# mcp23s08.net
KiCad netlist of a schematic drawn in EAGLE
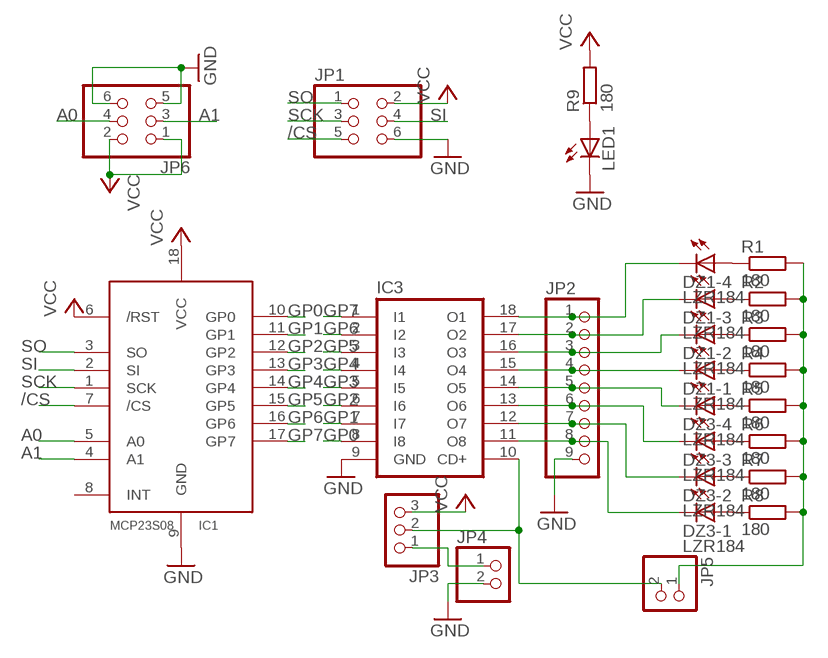
[diagram p0: schematic, sheet 1]

(export (version "E")
  (design (tool "Eeschema 10.0.6"))
  (components
    (comp (ref "DZ1")
      (value "LZR184")
      (footprint "eagle-import:LZR184")
      (libsource (lib "eagle-import") (part "LZR184"))
    )
    (comp (ref "DZ3")
      (value "LZR184")
      (footprint "eagle-import:LZR184")
      (libsource (lib "eagle-import") (part "LZR184"))
    )
    (comp (ref "IC1")
      (value "MCP2300X/P")
      (footprint "eagle-import:DIL18")
      (libsource (lib "eagle-import") (part "MCP2300X/P"))
    )
    (comp (ref "IC3")
      (value "ULN2803A")
      (footprint "eagle-import:DIL18")
      (libsource (lib "eagle-import") (part "ULN2803A"))
    )
    (comp (ref "JP1")
      (value "PINHD-2X3")
      (footprint "eagle-import:2X03")
      (libsource (lib "eagle-import") (part "PINHD-2X3"))
    )
    (comp (ref "JP2")
      (value "PINHD-1X9")
      (footprint "eagle-import:1X09")
      (libsource (lib "eagle-import") (part "PINHD-1X9"))
    )
    (comp (ref "JP3")
      (value "PINHD-1X3")
      (footprint "eagle-import:1X03")
      (libsource (lib "eagle-import") (part "PINHD-1X3"))
    )
    (comp (ref "JP4")
      (value "PINHD-1X2")
      (footprint "eagle-import:1X02")
      (libsource (lib "eagle-import") (part "PINHD-1X2"))
    )
    (comp (ref "JP5")
      (value "PINHD-1X2")
      (footprint "eagle-import:1X02")
      (libsource (lib "eagle-import") (part "PINHD-1X2"))
    )
    (comp (ref "JP6")
      (value "PINHD-2X3")
      (footprint "eagle-import:2X03")
      (libsource (lib "eagle-import") (part "PINHD-2X3"))
    )
    (comp (ref "LED1")
      (value "LED3MM")
      (footprint "eagle-import:LED3MM")
      (libsource (lib "eagle-import") (part "LED3MM"))
    )
    (comp (ref "R1")
      (value "180")
      (footprint "eagle-import:0204V")
      (libsource (lib "eagle-import") (part "R-EU_0204/2V"))
    )
    (comp (ref "R2")
      (value "180")
      (footprint "eagle-import:0204V")
      (libsource (lib "eagle-import") (part "R-EU_0204/2V"))
    )
    (comp (ref "R3")
      (value "180")
      (footprint "eagle-import:0204V")
      (libsource (lib "eagle-import") (part "R-EU_0204/2V"))
    )
    (comp (ref "R4")
      (value "180")
      (footprint "eagle-import:0204V")
      (libsource (lib "eagle-import") (part "R-EU_0204/2V"))
    )
    (comp (ref "R5")
      (value "180")
      (footprint "eagle-import:0204V")
      (libsource (lib "eagle-import") (part "R-EU_0204/2V"))
    )
    (comp (ref "R6")
      (value "180")
      (footprint "eagle-import:0204V")
      (libsource (lib "eagle-import") (part "R-EU_0204/2V"))
    )
    (comp (ref "R7")
      (value "180")
      (footprint "eagle-import:0204V")
      (libsource (lib "eagle-import") (part "R-EU_0204/2V"))
    )
    (comp (ref "R8")
      (value "180")
      (footprint "eagle-import:0204V")
      (libsource (lib "eagle-import") (part "R-EU_0204/2V"))
    )
    (comp (ref "R9")
      (value "180")
      (footprint "eagle-import:0204V")
      (libsource (lib "eagle-import") (part "R-EU_0204/2V"))
    )
  )
  (nets
    (net (code "1") (name "/A0") (class "Default")
      (node (ref "IC1") (pin "5") (pinfunction "A0_5") (pintype "input"))
      (node (ref "JP6") (pin "4") (pinfunction "4_4") (pintype "passive"))
    )
    (net (code "2") (name "/A1") (class "Default")
      (node (ref "IC1") (pin "4") (pinfunction "A1_4") (pintype "input"))
      (node (ref "JP6") (pin "3") (pinfunction "3_3") (pintype "passive"))
    )
    (net (code "3") (name "/GP0") (class "Default")
      (node (ref "IC1") (pin "10") (pinfunction "GP0_10") (pintype "bidirectional"))
      (node (ref "IC3") (pin "8") (pinfunction "I8_8") (pintype "input"))
    )
    (net (code "4") (name "/GP1") (class "Default")
      (node (ref "IC1") (pin "11") (pinfunction "GP1_11") (pintype "bidirectional"))
      (node (ref "IC3") (pin "7") (pinfunction "I7_7") (pintype "input"))
    )
    (net (code "5") (name "/GP2") (class "Default")
      (node (ref "IC1") (pin "12") (pinfunction "GP2_12") (pintype "bidirectional"))
      (node (ref "IC3") (pin "6") (pinfunction "I6_6") (pintype "input"))
    )
    (net (code "6") (name "/GP3") (class "Default")
      (node (ref "IC1") (pin "13") (pinfunction "GP3_13") (pintype "bidirectional"))
      (node (ref "IC3") (pin "5") (pinfunction "I5_5") (pintype "input"))
    )
    (net (code "7") (name "/GP4") (class "Default")
      (node (ref "IC1") (pin "14") (pinfunction "GP4_14") (pintype "bidirectional"))
      (node (ref "IC3") (pin "4") (pinfunction "I4_4") (pintype "input"))
    )
    (net (code "8") (name "/GP5") (class "Default")
      (node (ref "IC1") (pin "15") (pinfunction "GP5_15") (pintype "bidirectional"))
      (node (ref "IC3") (pin "3") (pinfunction "I3_3") (pintype "input"))
    )
    (net (code "9") (name "/GP6") (class "Default")
      (node (ref "IC1") (pin "16") (pinfunction "GP6_16") (pintype "bidirectional"))
      (node (ref "IC3") (pin "2") (pinfunction "I2_2") (pintype "input"))
    )
    (net (code "10") (name "/GP7") (class "Default")
      (node (ref "IC1") (pin "17") (pinfunction "GP7_17") (pintype "bidirectional"))
      (node (ref "IC3") (pin "1") (pinfunction "I1_1") (pintype "input"))
    )
    (net (code "11") (name "/SCK") (class "Default")
      (node (ref "IC1") (pin "1") (pinfunction "SCK_1") (pintype "bidirectional"))
      (node (ref "JP1") (pin "3") (pinfunction "3_3") (pintype "passive"))
    )
    (net (code "12") (name "/SI") (class "Default")
      (node (ref "IC1") (pin "2") (pinfunction "SI_2") (pintype "bidirectional"))
      (node (ref "JP1") (pin "4") (pinfunction "4_4") (pintype "passive"))
    )
    (net (code "13") (name "/SO") (class "Default")
      (node (ref "IC1") (pin "3") (pinfunction "SO_3") (pintype "output"))
      (node (ref "JP1") (pin "1") (pinfunction "1_1") (pintype "passive"))
    )
    (net (code "14") (name "/{slash}CS") (class "Default")
      (node (ref "IC1") (pin "7") (pinfunction "/CS_7") (pintype "input"))
      (node (ref "JP1") (pin "5") (pinfunction "5_5") (pintype "passive"))
    )
    (net (code "15") (name "GND") (class "Default")
      (node (ref "IC1") (pin "9") (pinfunction "GND_9") (pintype "power_in"))
      (node (ref "IC3") (pin "9") (pinfunction "GND_9") (pintype "power_in"))
      (node (ref "JP1") (pin "6") (pinfunction "6_6") (pintype "passive"))
      (node (ref "JP2") (pin "9") (pinfunction "9_9") (pintype "passive"))
      (node (ref "JP4") (pin "2") (pinfunction "2_2") (pintype "passive"))
      (node (ref "JP6") (pin "5") (pinfunction "5_5") (pintype "passive"))
      (node (ref "JP6") (pin "6") (pinfunction "6_6") (pintype "passive"))
      (node (ref "LED1") (pin "K") (pinfunction "C_K") (pintype "passive"))
    )
    (net (code "16") (name "Net-(DZ1A-A)") (class "Default")
      (node (ref "DZ1") (pin "A1") (pinfunction "A_A1") (pintype "passive"))
      (node (ref "R4") (pin "1") (pinfunction "1_1") (pintype "passive"))
    )
    (net (code "17") (name "Net-(DZ1A-C)") (class "Default")
      (node (ref "DZ1") (pin "K1") (pinfunction "C_K1") (pintype "passive"))
      (node (ref "IC3") (pin "15") (pinfunction "O4_15") (pintype "open_collector"))
      (node (ref "JP2") (pin "4") (pinfunction "4_4") (pintype "passive"))
    )
    (net (code "18") (name "Net-(DZ1B-A)") (class "Default")
      (node (ref "DZ1") (pin "A2") (pinfunction "A_A2") (pintype "passive"))
      (node (ref "R3") (pin "1") (pinfunction "1_1") (pintype "passive"))
    )
    (net (code "19") (name "Net-(DZ1B-C)") (class "Default")
      (node (ref "DZ1") (pin "K2") (pinfunction "C_K2") (pintype "passive"))
      (node (ref "IC3") (pin "16") (pinfunction "O3_16") (pintype "open_collector"))
      (node (ref "JP2") (pin "3") (pinfunction "3_3") (pintype "passive"))
    )
    (net (code "20") (name "Net-(DZ1C-A)") (class "Default")
      (node (ref "DZ1") (pin "A3") (pinfunction "A_A3") (pintype "passive"))
      (node (ref "R2") (pin "1") (pinfunction "1_1") (pintype "passive"))
    )
    (net (code "21") (name "Net-(DZ1C-C)") (class "Default")
      (node (ref "DZ1") (pin "K3") (pinfunction "C_K3") (pintype "passive"))
      (node (ref "IC3") (pin "17") (pinfunction "O2_17") (pintype "open_collector"))
      (node (ref "JP2") (pin "2") (pinfunction "2_2") (pintype "passive"))
    )
    (net (code "22") (name "Net-(DZ1D-A)") (class "Default")
      (node (ref "DZ1") (pin "A4") (pinfunction "A_A4") (pintype "passive"))
      (node (ref "R1") (pin "1") (pinfunction "1_1") (pintype "passive"))
    )
    (net (code "23") (name "Net-(DZ1D-C)") (class "Default")
      (node (ref "DZ1") (pin "K4") (pinfunction "C_K4") (pintype "passive"))
      (node (ref "IC3") (pin "18") (pinfunction "O1_18") (pintype "open_collector"))
      (node (ref "JP2") (pin "1") (pinfunction "1_1") (pintype "passive"))
    )
    (net (code "24") (name "Net-(DZ3A-A)") (class "Default")
      (node (ref "DZ3") (pin "A1") (pinfunction "A_A1") (pintype "passive"))
      (node (ref "R8") (pin "1") (pinfunction "1_1") (pintype "passive"))
    )
    (net (code "25") (name "Net-(DZ3A-C)") (class "Default")
      (node (ref "DZ3") (pin "K1") (pinfunction "C_K1") (pintype "passive"))
      (node (ref "IC3") (pin "11") (pinfunction "O8_11") (pintype "open_collector"))
      (node (ref "JP2") (pin "8") (pinfunction "8_8") (pintype "passive"))
    )
    (net (code "26") (name "Net-(DZ3B-A)") (class "Default")
      (node (ref "DZ3") (pin "A2") (pinfunction "A_A2") (pintype "passive"))
      (node (ref "R7") (pin "1") (pinfunction "1_1") (pintype "passive"))
    )
    (net (code "27") (name "Net-(DZ3B-C)") (class "Default")
      (node (ref "DZ3") (pin "K2") (pinfunction "C_K2") (pintype "passive"))
      (node (ref "IC3") (pin "12") (pinfunction "O7_12") (pintype "open_collector"))
      (node (ref "JP2") (pin "7") (pinfunction "7_7") (pintype "passive"))
    )
    (net (code "28") (name "Net-(DZ3C-A)") (class "Default")
      (node (ref "DZ3") (pin "A3") (pinfunction "A_A3") (pintype "passive"))
      (node (ref "R6") (pin "1") (pinfunction "1_1") (pintype "passive"))
    )
    (net (code "29") (name "Net-(DZ3C-C)") (class "Default")
      (node (ref "DZ3") (pin "K3") (pinfunction "C_K3") (pintype "passive"))
      (node (ref "IC3") (pin "13") (pinfunction "O6_13") (pintype "open_collector"))
      (node (ref "JP2") (pin "6") (pinfunction "6_6") (pintype "passive"))
    )
    (net (code "30") (name "Net-(DZ3D-A)") (class "Default")
      (node (ref "DZ3") (pin "A4") (pinfunction "A_A4") (pintype "passive"))
      (node (ref "R5") (pin "1") (pinfunction "1_1") (pintype "passive"))
    )
    (net (code "31") (name "Net-(DZ3D-C)") (class "Default")
      (node (ref "DZ3") (pin "K4") (pinfunction "C_K4") (pintype "passive"))
      (node (ref "IC3") (pin "14") (pinfunction "O5_14") (pintype "open_collector"))
      (node (ref "JP2") (pin "5") (pinfunction "5_5") (pintype "passive"))
    )
    (net (code "32") (name "Net-(IC3-CD+)") (class "Default")
      (node (ref "IC3") (pin "10") (pinfunction "CD+_10") (pintype "passive"))
      (node (ref "JP3") (pin "2") (pinfunction "2_2") (pintype "passive"))
      (node (ref "JP5") (pin "2") (pinfunction "2_2") (pintype "passive"))
    )
    (net (code "33") (name "Net-(JP3-Pad1)") (class "Default")
      (node (ref "JP3") (pin "1") (pinfunction "1_1") (pintype "passive"))
      (node (ref "JP4") (pin "1") (pinfunction "1_1") (pintype "passive"))
    )
    (net (code "34") (name "Net-(JP5-Pad1)") (class "Default")
      (node (ref "JP5") (pin "1") (pinfunction "1_1") (pintype "passive"))
      (node (ref "R1") (pin "2") (pinfunction "2_2") (pintype "passive"))
      (node (ref "R2") (pin "2") (pinfunction "2_2") (pintype "passive"))
      (node (ref "R3") (pin "2") (pinfunction "2_2") (pintype "passive"))
      (node (ref "R4") (pin "2") (pinfunction "2_2") (pintype "passive"))
      (node (ref "R5") (pin "2") (pinfunction "2_2") (pintype "passive"))
      (node (ref "R6") (pin "2") (pinfunction "2_2") (pintype "passive"))
      (node (ref "R7") (pin "2") (pinfunction "2_2") (pintype "passive"))
      (node (ref "R8") (pin "2") (pinfunction "2_2") (pintype "passive"))
    )
    (net (code "35") (name "Net-(LED1-PadA)") (class "Default")
      (node (ref "LED1") (pin "A") (pinfunction "A_A") (pintype "passive"))
      (node (ref "R9") (pin "1") (pinfunction "1_1") (pintype "passive"))
    )
    (net (code "36") (name "VCC") (class "Default")
      (node (ref "IC1") (pin "18") (pinfunction "VCC_18") (pintype "power_in"))
      (node (ref "IC1") (pin "6") (pinfunction "/RST_6") (pintype "input"))
      (node (ref "JP1") (pin "2") (pinfunction "2_2") (pintype "passive"))
      (node (ref "JP3") (pin "3") (pinfunction "3_3") (pintype "passive"))
      (node (ref "JP6") (pin "1") (pinfunction "1_1") (pintype "passive"))
      (node (ref "JP6") (pin "2") (pinfunction "2_2") (pintype "passive"))
      (node (ref "R9") (pin "2") (pinfunction "2_2") (pintype "passive"))
    )
    (net (code "37") (name "unconnected-(IC1-INT-Pad8)") (class "Default")
      (node (ref "IC1") (pin "8") (pinfunction "INT_8") (pintype "output"))
    )
  )
)
